# DigitalPotentiometers.net
KiCad netlist of a schematic drawn in Altium Designer
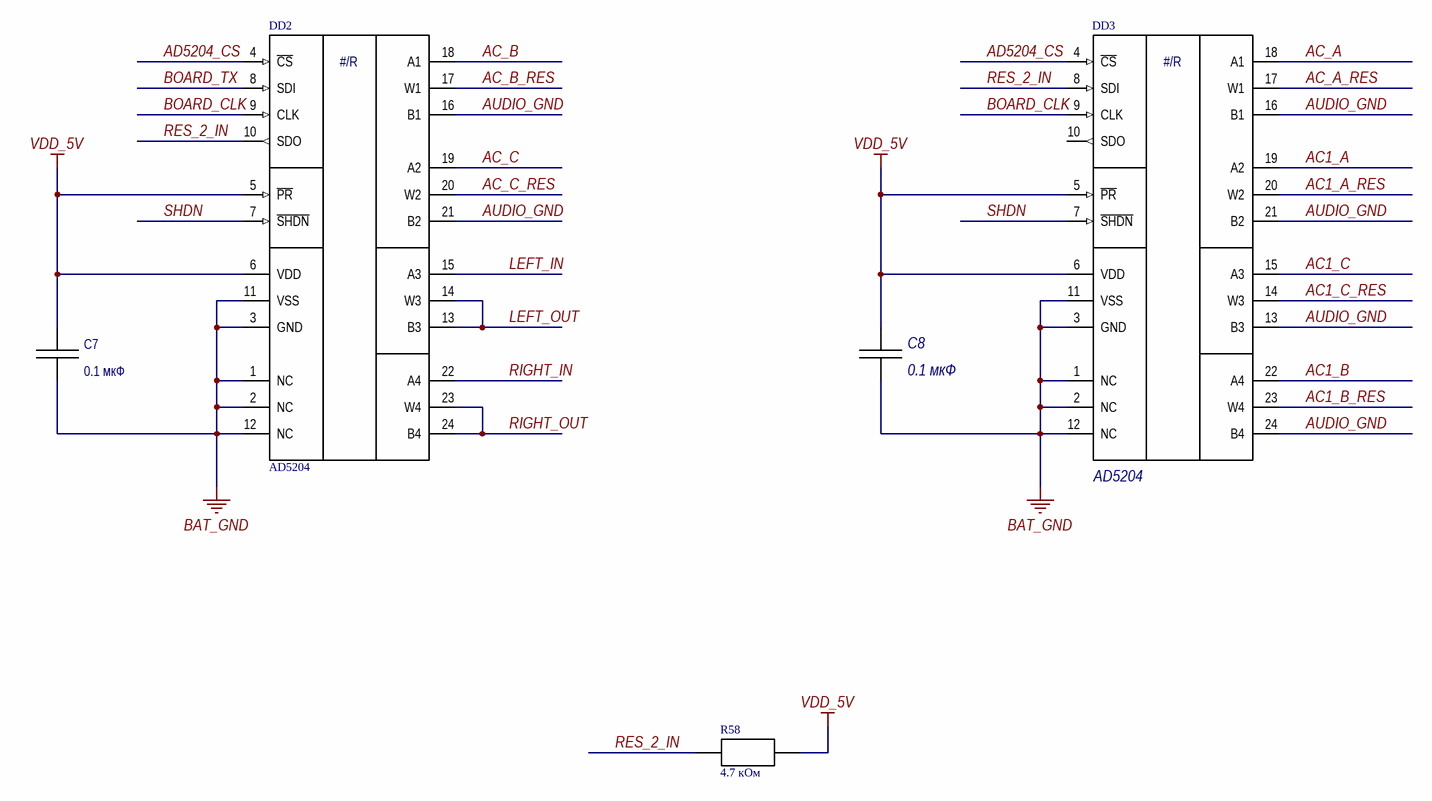
[diagram p0: DigitalPotentiometers.SchDoc]

(export (version "E")
  (design (tool "Eeschema 10.0.6"))
  (components
    (comp (ref "C7")
      (value "0.1 мкФ")
      (footprint "C 1206")
      (description "SMD Capacitor 1206")
      (fields
        (field (name "TOLERANCE") "/Укажите допуск в процентах/")
        (field (name "MANUFACTURER") "/Укажите компанию-производителя/")
      )
      (libsource (lib "my_lib") (part "CAP 1206"))
    )
    (comp (ref "C8")
      (value "0.1 мкФ")
      (footprint "C 1206")
      (description "SMD Capacitor 1206")
      (fields
        (field (name "TOLERANCE") "/Укажите допуск в процентах/")
        (field (name "MANUFACTURER") "/Укажите компанию-производителя/")
      )
      (libsource (lib "my_lib") (part "CAP 1206"))
    )
    (comp (ref "DD2") (value "AD5204") (footprint "TSSOP-24") (libsource (lib "my_lib") (part "AD5204")))
    (comp (ref "DD3") (value "AD5204") (footprint "TSSOP-24") (libsource (lib "my_lib") (part "AD5204")))
    (comp (ref "R58") (value "4.7 кОм") (footprint "RES 0805") (libsource (lib "my_lib") (part "RES 0805")))
  )
  (nets
    (net (code "1") (name "/AC1_A") (class "Default")
      (node (ref "DD3") (pin "19") (pinfunction "A2_19") (pintype "passive"))
    )
    (net (code "2") (name "/AC1_A_RES") (class "Default")
      (node (ref "DD3") (pin "20") (pinfunction "W2_20") (pintype "passive"))
    )
    (net (code "3") (name "/AC1_B") (class "Default")
      (node (ref "DD3") (pin "22") (pinfunction "A4_22") (pintype "passive"))
    )
    (net (code "4") (name "/AC1_B_RES") (class "Default")
      (node (ref "DD3") (pin "23") (pinfunction "W4_23") (pintype "passive"))
    )
    (net (code "5") (name "/AC1_C") (class "Default")
      (node (ref "DD3") (pin "15") (pinfunction "A3_15") (pintype "passive"))
    )
    (net (code "6") (name "/AC1_C_RES") (class "Default")
      (node (ref "DD3") (pin "14") (pinfunction "W3_14") (pintype "passive"))
    )
    (net (code "7") (name "/AC_A") (class "Default")
      (node (ref "DD3") (pin "18") (pinfunction "A1_18") (pintype "passive"))
    )
    (net (code "8") (name "/AC_A_RES") (class "Default")
      (node (ref "DD3") (pin "17") (pinfunction "W1_17") (pintype "passive"))
    )
    (net (code "9") (name "/AC_B") (class "Default")
      (node (ref "DD2") (pin "18") (pinfunction "A1_18") (pintype "passive"))
    )
    (net (code "10") (name "/AC_B_RES") (class "Default")
      (node (ref "DD2") (pin "17") (pinfunction "W1_17") (pintype "passive"))
    )
    (net (code "11") (name "/AC_C") (class "Default")
      (node (ref "DD2") (pin "19") (pinfunction "A2_19") (pintype "passive"))
    )
    (net (code "12") (name "/AC_C_RES") (class "Default")
      (node (ref "DD2") (pin "20") (pinfunction "W2_20") (pintype "passive"))
    )
    (net (code "13") (name "/AD5204_CS") (class "Default")
      (node (ref "DD2") (pin "4") (pinfunction "~{CS}_4") (pintype "input"))
      (node (ref "DD3") (pin "4") (pinfunction "~{CS}_4") (pintype "input"))
    )
    (net (code "14") (name "/AUDIO_GND") (class "Default")
      (node (ref "DD2") (pin "16") (pinfunction "B1_16") (pintype "passive"))
      (node (ref "DD2") (pin "21") (pinfunction "B2_21") (pintype "passive"))
      (node (ref "DD3") (pin "13") (pinfunction "B3_13") (pintype "passive"))
      (node (ref "DD3") (pin "16") (pinfunction "B1_16") (pintype "passive"))
      (node (ref "DD3") (pin "21") (pinfunction "B2_21") (pintype "passive"))
      (node (ref "DD3") (pin "24") (pinfunction "B4_24") (pintype "passive"))
    )
    (net (code "15") (name "/BOARD_CLK") (class "Default")
      (node (ref "DD2") (pin "9") (pinfunction "CLK_9") (pintype "input"))
      (node (ref "DD3") (pin "9") (pinfunction "CLK_9") (pintype "input"))
    )
    (net (code "16") (name "/BOARD_TX") (class "Default")
      (node (ref "DD2") (pin "8") (pinfunction "SDI_8") (pintype "input"))
    )
    (net (code "17") (name "/LEFT_IN") (class "Default")
      (node (ref "DD2") (pin "15") (pinfunction "A3_15") (pintype "passive"))
    )
    (net (code "18") (name "/LEFT_OUT") (class "Default")
      (node (ref "DD2") (pin "13") (pinfunction "B3_13") (pintype "passive"))
      (node (ref "DD2") (pin "14") (pinfunction "W3_14") (pintype "passive"))
    )
    (net (code "19") (name "/RES_2_IN") (class "Default")
      (node (ref "DD2") (pin "10") (pinfunction "SDO_10") (pintype "output"))
      (node (ref "DD3") (pin "8") (pinfunction "SDI_8") (pintype "input"))
      (node (ref "R58") (pin "1") (pinfunction "1_1") (pintype "passive"))
    )
    (net (code "20") (name "/RIGHT_IN") (class "Default")
      (node (ref "DD2") (pin "22") (pinfunction "A4_22") (pintype "passive"))
    )
    (net (code "21") (name "/RIGHT_OUT") (class "Default")
      (node (ref "DD2") (pin "23") (pinfunction "W4_23") (pintype "passive"))
      (node (ref "DD2") (pin "24") (pinfunction "B4_24") (pintype "passive"))
    )
    (net (code "22") (name "/SHDN") (class "Default")
      (node (ref "DD2") (pin "7") (pinfunction "~{SHDN}_7") (pintype "input"))
      (node (ref "DD3") (pin "7") (pinfunction "~{SHDN}_7") (pintype "input"))
    )
    (net (code "23") (name "BAT_GND") (class "Default")
      (node (ref "C7") (pin "2") (pinfunction "2_2") (pintype "passive"))
      (node (ref "C8") (pin "2") (pinfunction "2_2") (pintype "passive"))
      (node (ref "DD2") (pin "1") (pinfunction "NC_1") (pintype "passive"))
      (node (ref "DD2") (pin "11") (pinfunction "VSS_11") (pintype "power_in"))
      (node (ref "DD2") (pin "12") (pinfunction "NC_12") (pintype "passive"))
      (node (ref "DD2") (pin "2") (pinfunction "NC_2") (pintype "passive"))
      (node (ref "DD2") (pin "3") (pinfunction "GND_3") (pintype "power_in"))
      (node (ref "DD3") (pin "1") (pinfunction "NC_1") (pintype "passive"))
      (node (ref "DD3") (pin "11") (pinfunction "VSS_11") (pintype "power_in"))
      (node (ref "DD3") (pin "12") (pinfunction "NC_12") (pintype "passive"))
      (node (ref "DD3") (pin "2") (pinfunction "NC_2") (pintype "passive"))
      (node (ref "DD3") (pin "3") (pinfunction "GND_3") (pintype "power_in"))
    )
    (net (code "24") (name "VDD_5V") (class "Default")
      (node (ref "C7") (pin "1") (pinfunction "1_1") (pintype "passive"))
      (node (ref "C8") (pin "1") (pinfunction "1_1") (pintype "passive"))
      (node (ref "DD2") (pin "5") (pinfunction "~{PR}_5") (pintype "input"))
      (node (ref "DD2") (pin "6") (pinfunction "VDD_6") (pintype "power_in"))
      (node (ref "DD3") (pin "5") (pinfunction "~{PR}_5") (pintype "input"))
      (node (ref "DD3") (pin "6") (pinfunction "VDD_6") (pintype "power_in"))
      (node (ref "R58") (pin "2") (pinfunction "2_2") (pintype "passive"))
    )
    (net (code "25") (name "unconnected-(DD3-SDO-Pad10)") (class "Default")
      (node (ref "DD3") (pin "10") (pinfunction "SDO_10") (pintype "output"))
    )
  )
)
